# arduino_M_Pascal_Darmawan.net
KiCad netlist of a schematic drawn in EAGLE
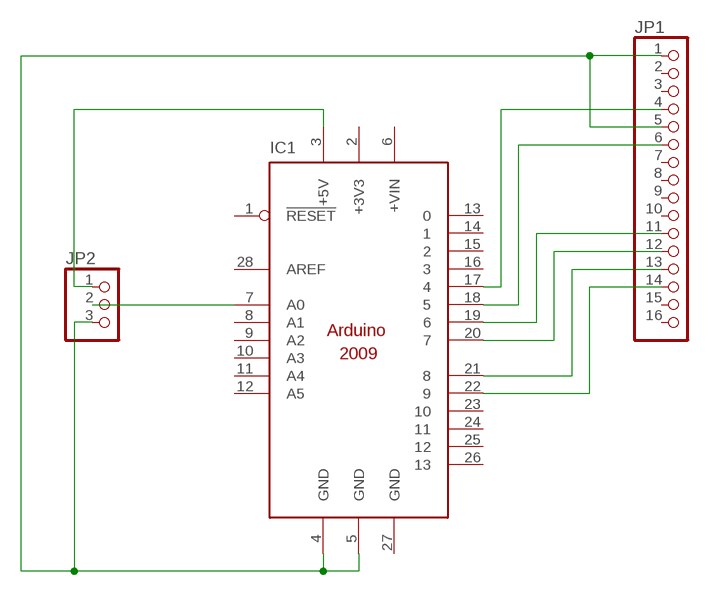
[diagram p0: schematic, sheet 1]

(export (version "E")
  (design (tool "Eeschema 10.0.6"))
  (components
    (comp (ref "IC1")
      (value "ARDUINO2009_12")
      (footprint "eagle-import:ARDUINO2009_2")
      (libsource (lib "eagle-import") (part "ARDUINO2009_12"))
    )
    (comp (ref "JP1")
      (value "PINHD-1X16")
      (footprint "eagle-import:1X16")
      (libsource (lib "eagle-import") (part "PINHD-1X16"))
    )
    (comp (ref "JP2")
      (value "PINHD-1X3")
      (footprint "eagle-import:1X03")
      (libsource (lib "eagle-import") (part "PINHD-1X3"))
    )
  )
  (nets
    (net (code "1") (name "/+3V3") (class "Default")
      (node (ref "IC1") (pin "2") (pinfunction "+3V3_2") (pintype "power_in"))
    )
    (net (code "2") (name "/GND") (class "Default")
      (node (ref "IC1") (pin "27") (pinfunction "GND_27") (pintype "power_in"))
    )
    (net (code "3") (name "Net-(IC1-+5V)") (class "Default")
      (node (ref "IC1") (pin "3") (pinfunction "+5V_3") (pintype "power_in"))
      (node (ref "JP2") (pin "1") (pinfunction "1_1") (pintype "passive"))
    )
    (net (code "4") (name "Net-(IC1-4)") (class "Default")
      (node (ref "IC1") (pin "17") (pinfunction "4_17") (pintype "bidirectional"))
      (node (ref "JP1") (pin "4") (pinfunction "4_4") (pintype "passive"))
    )
    (net (code "5") (name "Net-(IC1-5)") (class "Default")
      (node (ref "IC1") (pin "18") (pinfunction "5_18") (pintype "bidirectional"))
      (node (ref "JP1") (pin "6") (pinfunction "6_6") (pintype "passive"))
    )
    (net (code "6") (name "Net-(IC1-6)") (class "Default")
      (node (ref "IC1") (pin "19") (pinfunction "6_19") (pintype "bidirectional"))
      (node (ref "JP1") (pin "11") (pinfunction "11_11") (pintype "passive"))
    )
    (net (code "7") (name "Net-(IC1-7)") (class "Default")
      (node (ref "IC1") (pin "20") (pinfunction "7_20") (pintype "bidirectional"))
      (node (ref "JP1") (pin "12") (pinfunction "12_12") (pintype "passive"))
    )
    (net (code "8") (name "Net-(IC1-8)") (class "Default")
      (node (ref "IC1") (pin "21") (pinfunction "8_21") (pintype "bidirectional"))
      (node (ref "JP1") (pin "13") (pinfunction "13_13") (pintype "passive"))
    )
    (net (code "9") (name "Net-(IC1-9)") (class "Default")
      (node (ref "IC1") (pin "22") (pinfunction "9_22") (pintype "bidirectional"))
      (node (ref "JP1") (pin "14") (pinfunction "14_14") (pintype "passive"))
    )
    (net (code "10") (name "Net-(IC1-A0)") (class "Default")
      (node (ref "IC1") (pin "7") (pinfunction "A0_7") (pintype "bidirectional"))
      (node (ref "JP2") (pin "2") (pinfunction "2_2") (pintype "passive"))
    )
    (net (code "11") (name "Net-(IC1-GND-Pad4)") (class "Default")
      (node (ref "IC1") (pin "4") (pinfunction "GND_4") (pintype "power_in"))
      (node (ref "IC1") (pin "5") (pinfunction "GND_5") (pintype "power_in"))
      (node (ref "JP1") (pin "1") (pinfunction "1_1") (pintype "passive"))
      (node (ref "JP1") (pin "5") (pinfunction "5_5") (pintype "passive"))
      (node (ref "JP2") (pin "3") (pinfunction "3_3") (pintype "passive"))
    )
    (net (code "12") (name "unconnected-(IC1-+VIN-Pad6)") (class "Default")
      (node (ref "IC1") (pin "6") (pinfunction "+VIN_6") (pintype "bidirectional"))
    )
    (net (code "13") (name "unconnected-(IC1-0-Pad13)") (class "Default")
      (node (ref "IC1") (pin "13") (pinfunction "0_13") (pintype "bidirectional"))
    )
    (net (code "14") (name "unconnected-(IC1-1-Pad14)") (class "Default")
      (node (ref "IC1") (pin "14") (pinfunction "1_14") (pintype "bidirectional"))
    )
    (net (code "15") (name "unconnected-(IC1-2-Pad15)") (class "Default")
      (node (ref "IC1") (pin "15") (pinfunction "2_15") (pintype "bidirectional"))
    )
    (net (code "16") (name "unconnected-(IC1-3-Pad16)") (class "Default")
      (node (ref "IC1") (pin "16") (pinfunction "3_16") (pintype "bidirectional"))
    )
    (net (code "17") (name "unconnected-(IC1-10-Pad23)") (class "Default")
      (node (ref "IC1") (pin "23") (pinfunction "10_23") (pintype "bidirectional"))
    )
    (net (code "18") (name "unconnected-(IC1-11-Pad24)") (class "Default")
      (node (ref "IC1") (pin "24") (pinfunction "11_24") (pintype "bidirectional"))
    )
    (net (code "19") (name "unconnected-(IC1-12-Pad25)") (class "Default")
      (node (ref "IC1") (pin "25") (pinfunction "12_25") (pintype "bidirectional"))
    )
    (net (code "20") (name "unconnected-(IC1-13-Pad26)") (class "Default")
      (node (ref "IC1") (pin "26") (pinfunction "13_26") (pintype "bidirectional"))
    )
    (net (code "21") (name "unconnected-(IC1-A1-Pad8)") (class "Default")
      (node (ref "IC1") (pin "8") (pinfunction "A1_8") (pintype "bidirectional"))
    )
    (net (code "22") (name "unconnected-(IC1-A2-Pad9)") (class "Default")
      (node (ref "IC1") (pin "9") (pinfunction "A2_9") (pintype "bidirectional"))
    )
    (net (code "23") (name "unconnected-(IC1-A3-Pad10)") (class "Default")
      (node (ref "IC1") (pin "10") (pinfunction "A3_10") (pintype "bidirectional"))
    )
    (net (code "24") (name "unconnected-(IC1-A4-Pad11)") (class "Default")
      (node (ref "IC1") (pin "11") (pinfunction "A4_11") (pintype "bidirectional"))
    )
    (net (code "25") (name "unconnected-(IC1-A5-Pad12)") (class "Default")
      (node (ref "IC1") (pin "12") (pinfunction "A5_12") (pintype "bidirectional"))
    )
    (net (code "26") (name "unconnected-(IC1-AREF-Pad28)") (class "Default")
      (node (ref "IC1") (pin "28") (pinfunction "AREF_28") (pintype "bidirectional"))
    )
    (net (code "27") (name "unconnected-(IC1-~{RESET}-Pad1)") (class "Default")
      (node (ref "IC1") (pin "1") (pinfunction "~{RESET}_1") (pintype "bidirectional"))
    )
    (net (code "28") (name "unconnected-(JP1-Pad2)") (class "Default")
      (node (ref "JP1") (pin "2") (pinfunction "2_2") (pintype "passive"))
    )
    (net (code "29") (name "unconnected-(JP1-Pad3)") (class "Default")
      (node (ref "JP1") (pin "3") (pinfunction "3_3") (pintype "passive"))
    )
    (net (code "30") (name "unconnected-(JP1-Pad7)") (class "Default")
      (node (ref "JP1") (pin "7") (pinfunction "7_7") (pintype "passive"))
    )
    (net (code "31") (name "unconnected-(JP1-Pad8)") (class "Default")
      (node (ref "JP1") (pin "8") (pinfunction "8_8") (pintype "passive"))
    )
    (net (code "32") (name "unconnected-(JP1-Pad9)") (class "Default")
      (node (ref "JP1") (pin "9") (pinfunction "9_9") (pintype "passive"))
    )
    (net (code "33") (name "unconnected-(JP1-Pad10)") (class "Default")
      (node (ref "JP1") (pin "10") (pinfunction "10_10") (pintype "passive"))
    )
    (net (code "34") (name "unconnected-(JP1-Pad15)") (class "Default")
      (node (ref "JP1") (pin "15") (pinfunction "15_15") (pintype "passive"))
    )
    (net (code "35") (name "unconnected-(JP1-Pad16)") (class "Default")
      (node (ref "JP1") (pin "16") (pinfunction "16_16") (pintype "passive"))
    )
  )
)
